# DC-DC_Buck_Converter_12Vto_3_3V.net
KiCad netlist of a schematic drawn in Altium Designer
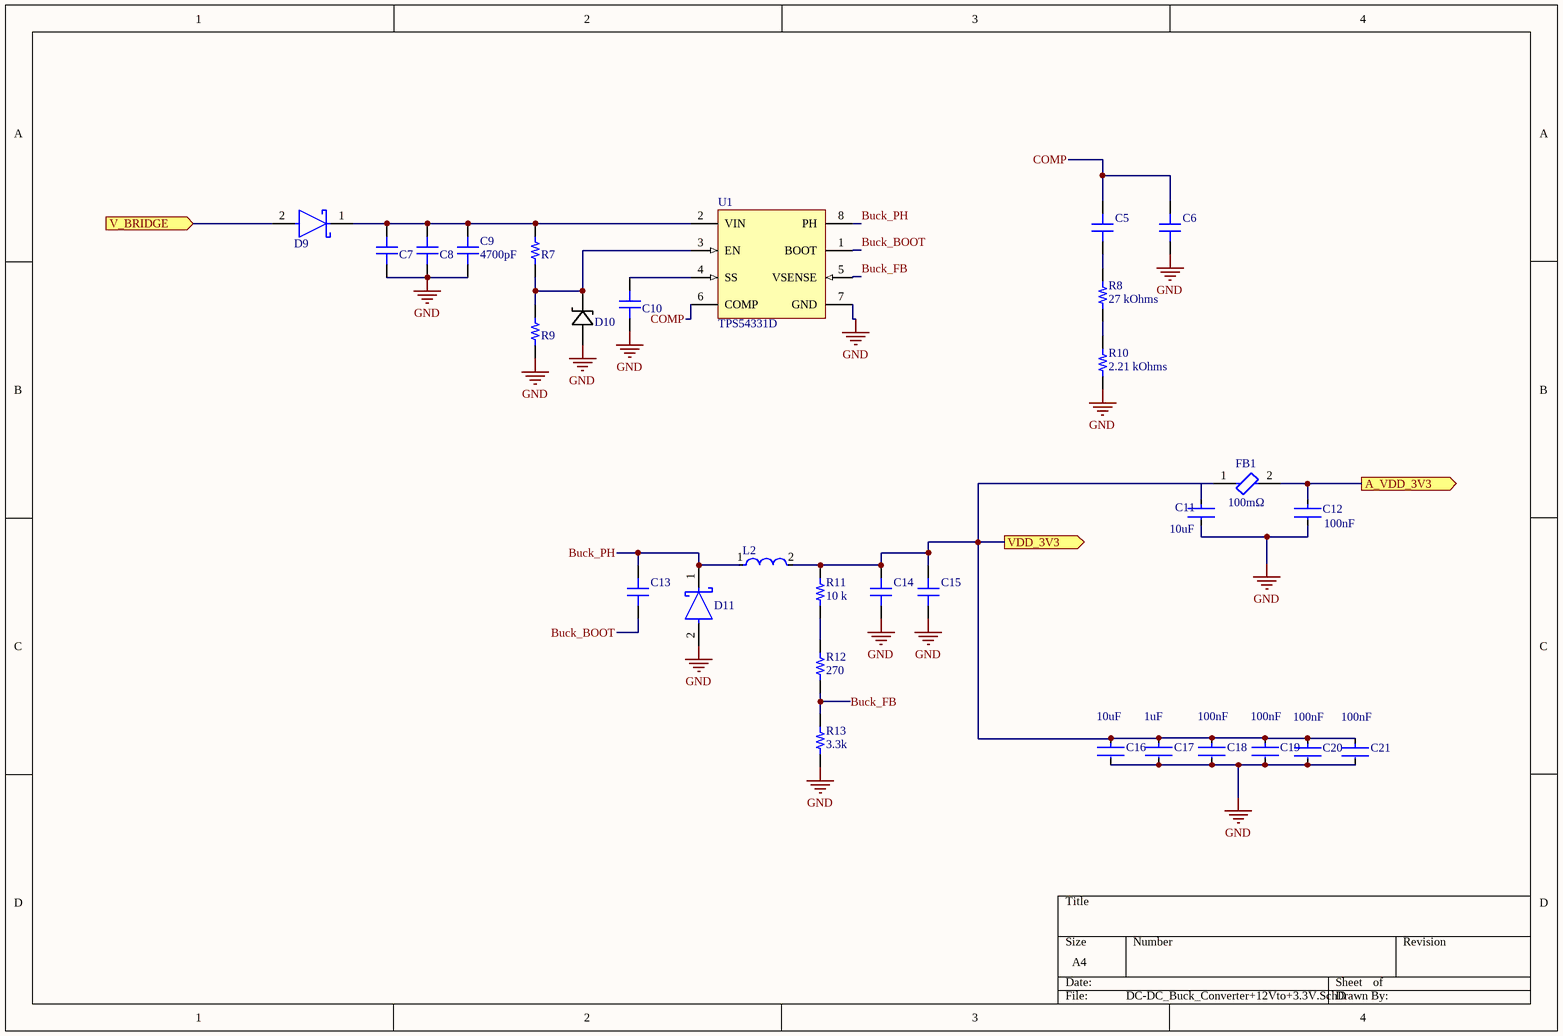
[diagram p0: DC-DC_Buck_Converter+12Vto+3.3V.SchDoc]

(export (version "E")
  (design (tool "Eeschema 10.0.6"))
  (components
    (comp (ref "C5")
      (value "4700pF")
      (footprint "CAP 0603_1608")
      (description "CAP CER 4700PF 50V X7R 0603")
      (fields (field (name "PART NUMBER") "06035C472JAT2A") (field (name "MANUFACTURER") "AVX Corporation"))
      (libsource (lib "Celestial Altium Library - altium_library (4)") (part "Capacitor"))
    )
    (comp (ref "C6")
      (value "4700pF")
      (footprint "CAP 0603_1608")
      (description "CAP CER 4700PF 50V X7R 0603")
      (fields (field (name "PART NUMBER") "06035C472JAT2A") (field (name "MANUFACTURER") "AVX Corporation"))
      (libsource (lib "Celestial Altium Library - altium_library (4)") (part "Capacitor"))
    )
    (comp (ref "C7")
      (value "4700pF")
      (footprint "CAP 0603_1608")
      (description "CAP CER 4700PF 50V X7R 0603")
      (fields (field (name "PART NUMBER") "06035C472JAT2A") (field (name "MANUFACTURER") "AVX Corporation"))
      (libsource (lib "Celestial Altium Library - altium_library (4)") (part "Capacitor"))
    )
    (comp (ref "C8")
      (value "4700pF")
      (footprint "CAP 0603_1608")
      (description "CAP CER 4700PF 50V X7R 0603")
      (fields (field (name "PART NUMBER") "06035C472JAT2A") (field (name "MANUFACTURER") "AVX Corporation"))
      (libsource (lib "Celestial Altium Library - altium_library (4)") (part "Capacitor"))
    )
    (comp (ref "C9")
      (value "4700pF")
      (footprint "CAP 0603_1608")
      (description "CAP CER 4700PF 50V X7R 0603")
      (fields (field (name "PART NUMBER") "06035C472JAT2A") (field (name "MANUFACTURER") "AVX Corporation"))
      (libsource (lib "Celestial Altium Library - altium_library (4)") (part "Capacitor"))
    )
    (comp (ref "C10")
      (value "4700pF")
      (footprint "CAP 0603_1608")
      (description "CAP CER 4700PF 50V X7R 0603")
      (fields (field (name "PART NUMBER") "06035C472JAT2A") (field (name "MANUFACTURER") "AVX Corporation"))
      (libsource (lib "Celestial Altium Library - altium_library (4)") (part "Capacitor"))
    )
    (comp (ref "C11")
      (value "GRM188R60J106ME47D")
      (footprint "FP-GRM188-0_1-e0_2_0_55-IPC_A")
      (description "Chip Multilayer Ceramic Capacitors for General Purpose, 0603, 10uF, X5R, 15%, 20%, 6.3V")
      (fields
        (field (name "CAPACITANCE") "10uF")
        (field (name "VOLTAGE") "6.3V")
        (field (name "TOLERANCE") "20%")
      )
      (libsource (lib "Altium Content Vault") (part "02cd4be3c70576c341d710602a673aa"))
    )
    (comp (ref "C12")
      (value "GRM033R60J104KE19D")
      (footprint "FP-GRM033-0_03-MFG")
      (description "Chip Multilayer Ceramic Capacitors for General Purpose, 0201, 0.10uF, X5R, 15%, 10%, 6.3V")
      (fields
        (field (name "CAPACITANCE") "100nF")
        (field (name "VOLTAGE") "6.3V")
        (field (name "TOLERANCE") "10%")
      )
      (libsource (lib "Altium Content Vault") (part "b4654b650e69147ec39a6b967a45e02"))
    )
    (comp (ref "C13")
      (value "1000pF")
      (footprint "CAP 0603_1608")
      (description "CAP CER 1000PF 10V X7R 0603")
      (fields (field (name "PART NUMBER") "0603ZC102KAT2A") (field (name "MANUFACTURER") "AVX Corporation"))
      (libsource (lib "Celestial Altium Library - altium_library (4)") (part "Capacitor"))
    )
    (comp (ref "C14")
      (value "1000pF")
      (footprint "CAP 0603_1608")
      (description "CAP CER 1000PF 10V X7R 0603")
      (fields (field (name "PART NUMBER") "0603ZC102KAT2A") (field (name "MANUFACTURER") "AVX Corporation"))
      (libsource (lib "Celestial Altium Library - altium_library (4)") (part "Capacitor"))
    )
    (comp (ref "C15")
      (value "1000pF")
      (footprint "CAP 0603_1608")
      (description "CAP CER 1000PF 10V X7R 0603")
      (fields (field (name "PART NUMBER") "0603ZC102KAT2A") (field (name "MANUFACTURER") "AVX Corporation"))
      (libsource (lib "Celestial Altium Library - altium_library (4)") (part "Capacitor"))
    )
    (comp (ref "C16")
      (value "GRM188R60J106ME47D")
      (footprint "FP-GRM188-0_1-e0_2_0_55-IPC_A")
      (description "Chip Multilayer Ceramic Capacitors for General Purpose, 0603, 10uF, X5R, 15%, 20%, 6.3V")
      (fields
        (field (name "CAPACITANCE") "10uF")
        (field (name "VOLTAGE") "6.3V")
        (field (name "TOLERANCE") "20%")
      )
      (libsource (lib "Altium Content Vault") (part "02cd4be3c70576c341d710602a673aa"))
    )
    (comp (ref "C17")
      (value "1uF")
      (footprint "FP-GRM15-0_1-MFG")
      (description "CAP CER 1UF 10V X5R 0402")
      (fields
        (field (name "OCTOPART") "https://octopart.com/grm155r61a105ke15d-murata-197442")
        (field (name "MANUFACTURER PART NUMBER") "GRM155R61A105KE15D")
      )
      (libsource (lib "Altium Content Vault") (part "02cd4be3c70576c341d710602a673aa"))
    )
    (comp (ref "C18")
      (value "GRM033R60J104KE19D")
      (footprint "FP-GRM033-0_03-MFG")
      (description "Chip Multilayer Ceramic Capacitors for General Purpose, 0201, 0.10uF, X5R, 15%, 10%, 6.3V")
      (fields
        (field (name "CAPACITANCE") "100nF")
        (field (name "VOLTAGE") "6.3V")
        (field (name "TOLERANCE") "10%")
      )
      (libsource (lib "Altium Content Vault") (part "b4654b650e69147ec39a6b967a45e02"))
    )
    (comp (ref "C19")
      (value "GRM033R60J104KE19D")
      (footprint "FP-GRM033-0_03-MFG")
      (description "Chip Multilayer Ceramic Capacitors for General Purpose, 0201, 0.10uF, X5R, 15%, 10%, 6.3V")
      (fields
        (field (name "CAPACITANCE") "100nF")
        (field (name "VOLTAGE") "6.3V")
        (field (name "TOLERANCE") "10%")
      )
      (libsource (lib "Altium Content Vault") (part "b4654b650e69147ec39a6b967a45e02"))
    )
    (comp (ref "C20")
      (value "GRM033R60J104KE19D")
      (footprint "FP-GRM033-0_03-MFG")
      (description "Chip Multilayer Ceramic Capacitors for General Purpose, 0201, 0.10uF, X5R, 15%, 10%, 6.3V")
      (fields
        (field (name "CAPACITANCE") "100nF")
        (field (name "VOLTAGE") "6.3V")
        (field (name "TOLERANCE") "10%")
      )
      (libsource (lib "Altium Content Vault") (part "b4654b650e69147ec39a6b967a45e02"))
    )
    (comp (ref "C21")
      (value "GRM033R60J104KE19D")
      (footprint "FP-GRM033-0_03-MFG")
      (description "Chip Multilayer Ceramic Capacitors for General Purpose, 0201, 0.10uF, X5R, 15%, 10%, 6.3V")
      (fields
        (field (name "CAPACITANCE") "100nF")
        (field (name "VOLTAGE") "6.3V")
        (field (name "TOLERANCE") "10%")
      )
      (libsource (lib "Altium Content Vault") (part "b4654b650e69147ec39a6b967a45e02"))
    )
    (comp (ref "D9")
      (value "SS34-E3/57T")
      (footprint "FP-95402-MFG")
      (description "DIODE SCHOTTKY 40V 3A DO214AB")
      (fields
        (field (name "MANUFACTURER") "Vishay")
        (field (name "OCTOPART") "https://octopart.com/ss34-e3%2F57t-vishay-39552907")
      )
      (libsource (lib "Altium Content Vault") (part "1d6ec82d83fb6aee721767c19dac4b9"))
    )
    (comp (ref "D10") (value "zmm3v3") (footprint "zmm5v6") (libsource (lib "Schlib1") (part "zmm5v6")))
    (comp (ref "D11")
      (value "SS34-E3/57T")
      (footprint "FP-95402-MFG")
      (description "DIODE SCHOTTKY 40V 3A DO214AB")
      (fields
        (field (name "MANUFACTURER") "Vishay")
        (field (name "OCTOPART") "https://octopart.com/ss34-e3%2F57t-vishay-39552907")
      )
      (libsource (lib "Altium Content Vault") (part "1d6ec82d83fb6aee721767c19dac4b9"))
    )
    (comp (ref "FB1")
      (value "MPZ2012S601AT000")
      (footprint "FP-MPZ2012-MFG")
      (fields (field (name "TOLERANCE") "25%") (field (name "RESISTANCE") "100mΩ"))
      (libsource (lib "Altium Content Vault") (part "5f30dd21d616792df468990f7003faa"))
    )
    (comp (ref "L2")
      (value "IHLP2525CZER6R8M01")
      (footprint "FP-IHLP-2525CZ-FP_2_413x3-MFG")
      (description "Commercial Inductors, High Saturation Series 6.8uH 4.5A 60mΩ 20%")
      (fields (field (name "TOLERANCE") "20%"))
      (libsource (lib "Altium Content Vault") (part "725321dda6339637d4d059423bc1c3c"))
    )
    (comp (ref "R7")
      (value "15 kOhms")
      (footprint "RES 0805_2012")
      (description "PTN0805 10PPM 15K 0.1% S T1 E1")
      (fields
        (field (name "PART NUMBER") "PTN0805Y1502BST1")
        (field (name "MANUFACTURER") "Vishay Dale Thin Film")
      )
      (libsource (lib "Celestial Altium Library - altium_library (4)") (part "Resistor"))
    )
    (comp (ref "R8")
      (value "27 kOhms")
      (footprint "RES 0805_2012")
      (description "RES 27K OHM 1% 1/8W 0805")
      (fields
        (field (name "PART NUMBER") "RMCF0805FT27K0")
        (field (name "MANUFACTURER") "Stackpole Electronics Inc")
      )
      (libsource (lib "Celestial Altium Library - altium_library (4)") (part "Resistor"))
    )
    (comp (ref "R9")
      (value "15 kOhms")
      (footprint "RES 0805_2012")
      (description "PTN0805 10PPM 15K 0.1% S T1 E1")
      (fields
        (field (name "PART NUMBER") "PTN0805Y1502BST1")
        (field (name "MANUFACTURER") "Vishay Dale Thin Film")
      )
      (libsource (lib "Celestial Altium Library - altium_library (4)") (part "Resistor"))
    )
    (comp (ref "R10")
      (value "2.21 kOhms")
      (footprint "RES 0805_2012")
      (description "RES 2.21K OHM 1% 1/8W 0805")
      (fields
        (field (name "PART NUMBER") "RMCF0805FG2K21")
        (field (name "MANUFACTURER") "Stackpole Electronics Inc")
      )
      (libsource (lib "Celestial Altium Library - altium_library (4)") (part "Resistor"))
    )
    (comp (ref "R11")
      (value "10 k")
      (footprint "RES 0805_2012")
      (description "RES 27K OHM 1% 1/8W 0805")
      (fields
        (field (name "PART NUMBER") "RMCF0805FT27K0")
        (field (name "MANUFACTURER") "Stackpole Electronics Inc")
      )
      (libsource (lib "Celestial Altium Library - altium_library (4)") (part "Resistor"))
    )
    (comp (ref "R12")
      (value "270")
      (footprint "RES 0805_2012")
      (description "RES 27K OHM 1% 1/8W 0805")
      (fields
        (field (name "PART NUMBER") "RMCF0805FT27K0")
        (field (name "MANUFACTURER") "Stackpole Electronics Inc")
      )
      (libsource (lib "Celestial Altium Library - altium_library (4)") (part "Resistor"))
    )
    (comp (ref "R13")
      (value "3.3k")
      (footprint "RES 0805_2012")
      (description "RES 27K OHM 1% 1/8W 0805")
      (fields
        (field (name "PART NUMBER") "RMCF0805FT27K0")
        (field (name "MANUFACTURER") "Stackpole Electronics Inc")
      )
      (libsource (lib "Celestial Altium Library - altium_library (4)") (part "Resistor"))
    )
    (comp (ref "U1")
      (value "TPS54331D")
      (footprint "D0008A_L")
      (fields (field (name "MANUFACTURER") "Texas Instruments"))
      (libsource (lib "Altium Content Vault") (part "TI-TPS54331D8"))
    )
  )
  (nets
    (net (code "1") (name "/A_VDD_3V3") (class "Default")
      (node (ref "C12") (pin "1") (pinfunction "1_1") (pintype "passive"))
      (node (ref "FB1") (pin "2") (pinfunction "2_2") (pintype "passive"))
    )
    (net (code "2") (name "/Buck_BOOT") (class "Default")
      (node (ref "C13") (pin "2") (pinfunction "2_2") (pintype "passive"))
      (node (ref "U1") (pin "1") (pinfunction "BOOT_1") (pintype "passive"))
    )
    (net (code "3") (name "/Buck_FB") (class "Default")
      (node (ref "R12") (pin "1") (pinfunction "1_1") (pintype "passive"))
      (node (ref "R13") (pin "2") (pinfunction "2_2") (pintype "passive"))
      (node (ref "U1") (pin "5") (pinfunction "VSENSE_5") (pintype "input"))
    )
    (net (code "4") (name "/Buck_PH") (class "Default")
      (node (ref "C13") (pin "1") (pinfunction "1_1") (pintype "passive"))
      (node (ref "D11") (pin "1") (pinfunction "C_1") (pintype "passive"))
      (node (ref "L2") (pin "1") (pinfunction "1_1") (pintype "passive"))
      (node (ref "U1") (pin "8") (pinfunction "PH_8") (pintype "power_in"))
    )
    (net (code "5") (name "/COMP") (class "Default")
      (node (ref "C5") (pin "2") (pinfunction "2_2") (pintype "passive"))
      (node (ref "C6") (pin "2") (pinfunction "2_2") (pintype "passive"))
      (node (ref "U1") (pin "6") (pinfunction "COMP_6") (pintype "passive"))
    )
    (net (code "6") (name "/VDD_3V3") (class "Default")
      (node (ref "C11") (pin "1") (pinfunction "1_1") (pintype "passive"))
      (node (ref "C14") (pin "1") (pinfunction "1_1") (pintype "passive"))
      (node (ref "C15") (pin "1") (pinfunction "1_1") (pintype "passive"))
      (node (ref "C16") (pin "1") (pinfunction "1_1") (pintype "passive"))
      (node (ref "C17") (pin "1") (pinfunction "1_1") (pintype "passive"))
      (node (ref "C18") (pin "1") (pinfunction "1_1") (pintype "passive"))
      (node (ref "C19") (pin "1") (pinfunction "1_1") (pintype "passive"))
      (node (ref "C20") (pin "1") (pinfunction "1_1") (pintype "passive"))
      (node (ref "C21") (pin "1") (pinfunction "1_1") (pintype "passive"))
      (node (ref "FB1") (pin "1") (pinfunction "1_1") (pintype "passive"))
      (node (ref "L2") (pin "2") (pinfunction "2_2") (pintype "passive"))
      (node (ref "R11") (pin "2") (pinfunction "2_2") (pintype "passive"))
    )
    (net (code "7") (name "/V_BRIDGE") (class "Default")
      (node (ref "D9") (pin "2") (pinfunction "A_2") (pintype "passive"))
    )
    (net (code "8") (name "GND") (class "Default")
      (node (ref "C10") (pin "1") (pinfunction "1_1") (pintype "passive"))
      (node (ref "C11") (pin "2") (pinfunction "2_2") (pintype "passive"))
      (node (ref "C12") (pin "2") (pinfunction "2_2") (pintype "passive"))
      (node (ref "C14") (pin "2") (pinfunction "2_2") (pintype "passive"))
      (node (ref "C15") (pin "2") (pinfunction "2_2") (pintype "passive"))
      (node (ref "C16") (pin "2") (pinfunction "2_2") (pintype "passive"))
      (node (ref "C17") (pin "2") (pinfunction "2_2") (pintype "passive"))
      (node (ref "C18") (pin "2") (pinfunction "2_2") (pintype "passive"))
      (node (ref "C19") (pin "2") (pinfunction "2_2") (pintype "passive"))
      (node (ref "C20") (pin "2") (pinfunction "2_2") (pintype "passive"))
      (node (ref "C21") (pin "2") (pinfunction "2_2") (pintype "passive"))
      (node (ref "C6") (pin "1") (pinfunction "1_1") (pintype "passive"))
      (node (ref "C7") (pin "1") (pinfunction "1_1") (pintype "passive"))
      (node (ref "C8") (pin "1") (pinfunction "1_1") (pintype "passive"))
      (node (ref "C9") (pin "1") (pinfunction "1_1") (pintype "passive"))
      (node (ref "D10") (pin "2") (pinfunction "ANODE_2") (pintype "passive"))
      (node (ref "D11") (pin "2") (pinfunction "A_2") (pintype "passive"))
      (node (ref "R10") (pin "1") (pinfunction "1_1") (pintype "passive"))
      (node (ref "R13") (pin "1") (pinfunction "1_1") (pintype "passive"))
      (node (ref "R9") (pin "1") (pinfunction "1_1") (pintype "passive"))
      (node (ref "U1") (pin "7") (pinfunction "GND_7") (pintype "power_in"))
    )
    (net (code "9") (name "Net-(C5-Pad1)") (class "Default")
      (node (ref "C5") (pin "1") (pinfunction "1_1") (pintype "passive"))
      (node (ref "R8") (pin "2") (pinfunction "2_2") (pintype "passive"))
    )
    (net (code "10") (name "Net-(D9-C)") (class "Default")
      (node (ref "C7") (pin "2") (pinfunction "2_2") (pintype "passive"))
      (node (ref "C8") (pin "2") (pinfunction "2_2") (pintype "passive"))
      (node (ref "C9") (pin "2") (pinfunction "2_2") (pintype "passive"))
      (node (ref "D9") (pin "1") (pinfunction "C_1") (pintype "passive"))
      (node (ref "R7") (pin "2") (pinfunction "2_2") (pintype "passive"))
      (node (ref "U1") (pin "2") (pinfunction "VIN_2") (pintype "power_in"))
    )
    (net (code "11") (name "Net-(D10-CATHODE)") (class "Default")
      (node (ref "D10") (pin "1") (pinfunction "CATHODE_1") (pintype "passive"))
      (node (ref "R7") (pin "1") (pinfunction "1_1") (pintype "passive"))
      (node (ref "R9") (pin "2") (pinfunction "2_2") (pintype "passive"))
      (node (ref "U1") (pin "3") (pinfunction "EN_3") (pintype "input"))
    )
    (net (code "12") (name "Net-(R10-Pad2)") (class "Default")
      (node (ref "R10") (pin "2") (pinfunction "2_2") (pintype "passive"))
      (node (ref "R8") (pin "1") (pinfunction "1_1") (pintype "passive"))
    )
    (net (code "13") (name "Net-(R11-Pad1)") (class "Default")
      (node (ref "R11") (pin "1") (pinfunction "1_1") (pintype "passive"))
      (node (ref "R12") (pin "2") (pinfunction "2_2") (pintype "passive"))
    )
    (net (code "14") (name "Net-(U1-SS)") (class "Default")
      (node (ref "C10") (pin "2") (pinfunction "2_2") (pintype "passive"))
      (node (ref "U1") (pin "4") (pinfunction "SS_4") (pintype "input"))
    )
  )
)
